# subtractor-amp03_p-stm_v1_0.net
KiCad netlist of a schematic drawn in EAGLE
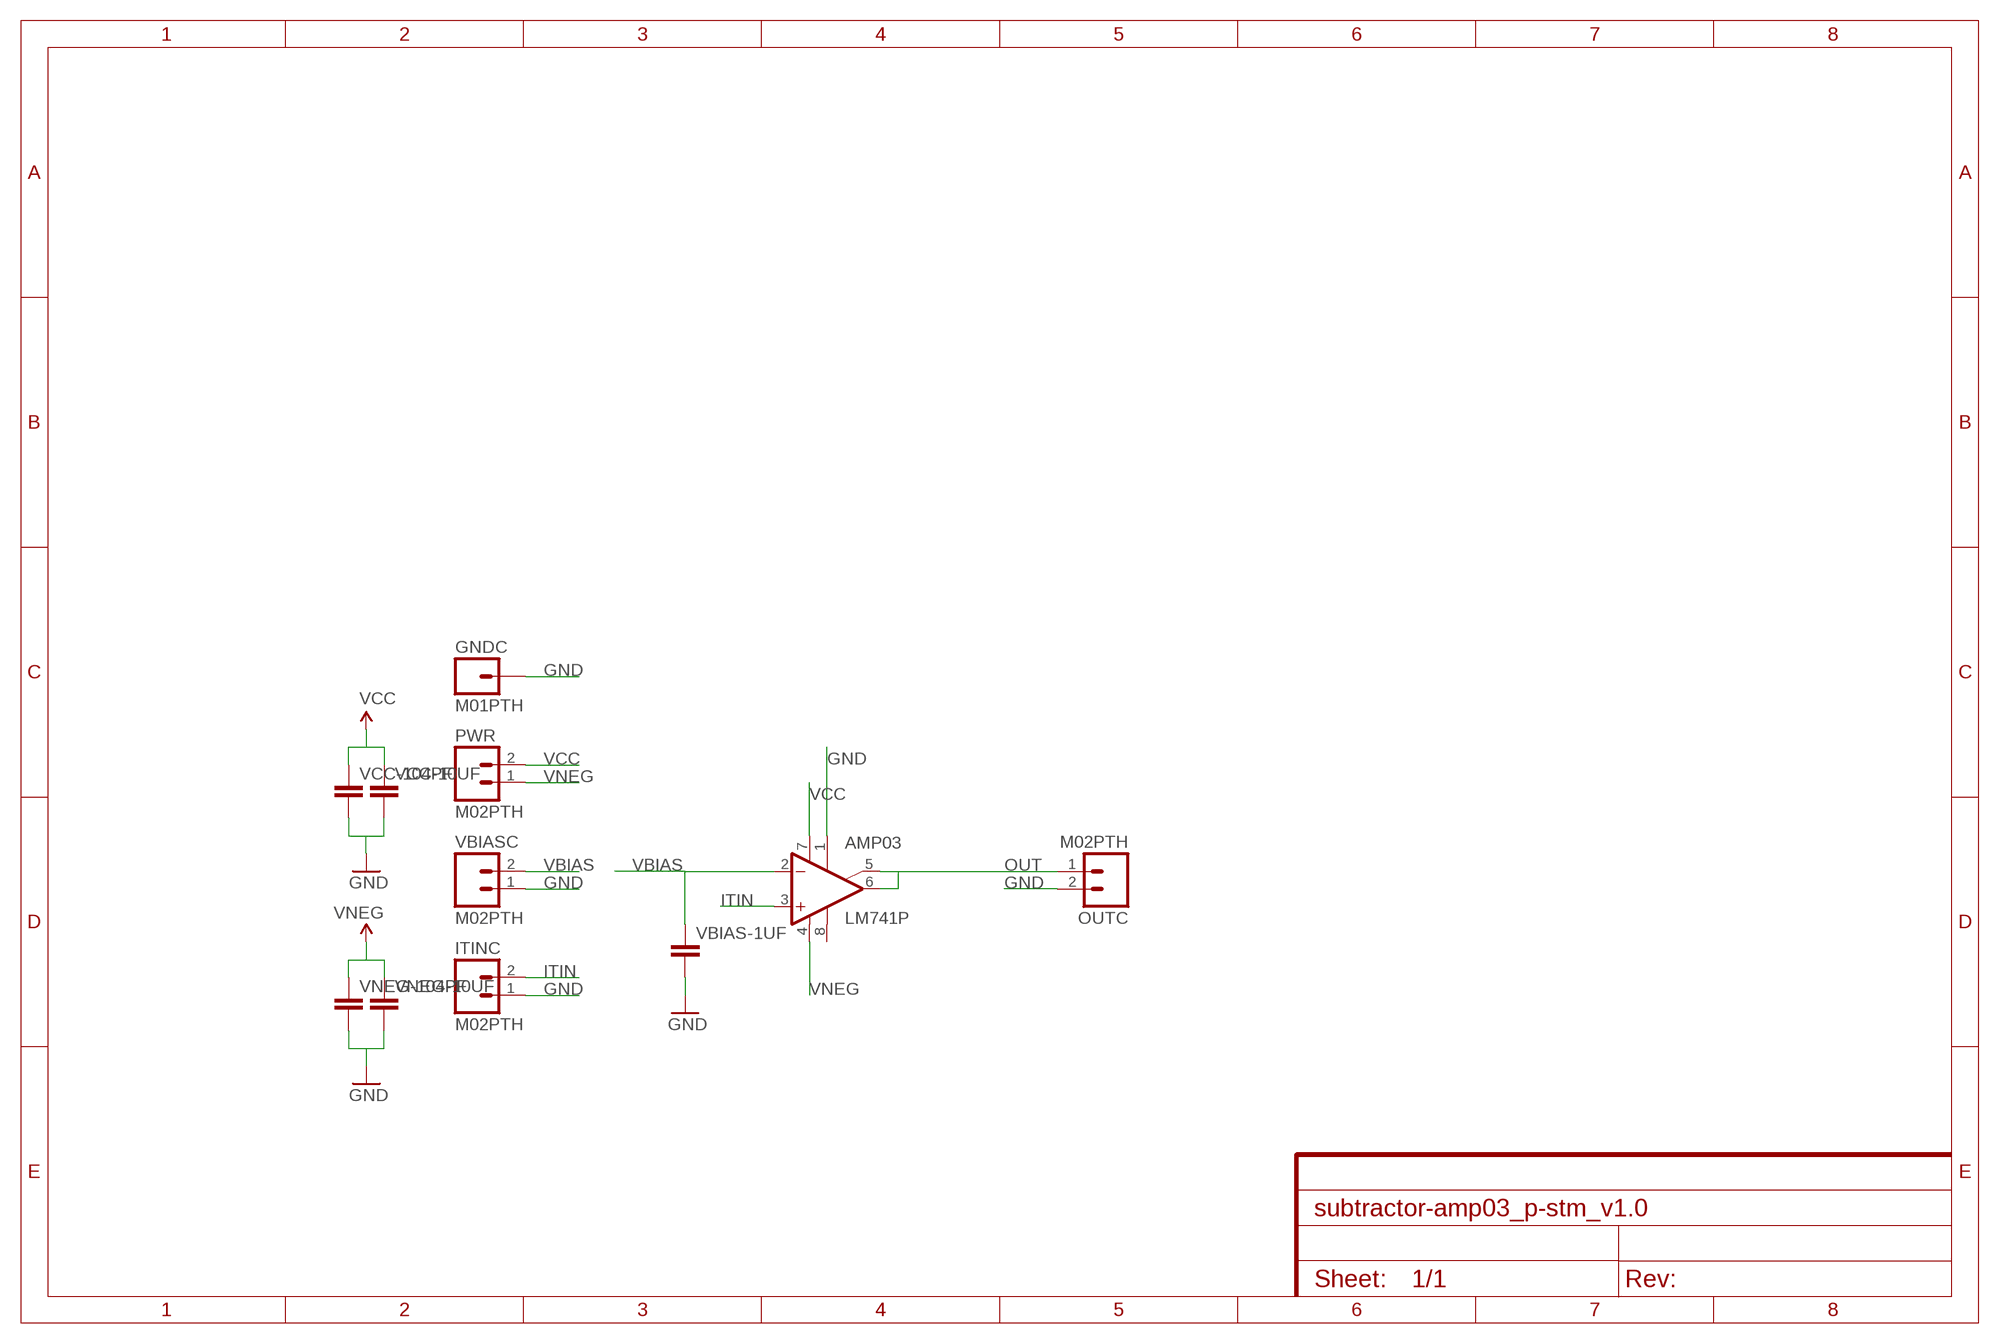
[diagram p0: schematic, sheet 1]

(export (version "E")
  (design (tool "Eeschema 10.0.6"))
  (components
    (comp (ref "AMP03")
      (value "LM741P")
      (footprint "eagle-import:DIL08")
      (libsource (lib "eagle-import") (part "741PLM"))
    )
    (comp (ref "GNDC")
      (value "M01PTH")
      (footprint "eagle-import:1X01")
      (libsource (lib "eagle-import") (part "M01PTH"))
    )
    (comp (ref "ITINC")
      (value "M02PTH")
      (footprint "eagle-import:1X02")
      (libsource (lib "eagle-import") (part "M02PTH"))
    )
    (comp (ref "OUTC")
      (value "M02PTH")
      (footprint "eagle-import:1X02")
      (libsource (lib "eagle-import") (part "M02PTH"))
    )
    (comp (ref "PWR")
      (value "M02PTH")
      (footprint "eagle-import:1X02")
      (libsource (lib "eagle-import") (part "M02PTH"))
    )
    (comp (ref "VBIAS-1UF")
      (value "CAPPTH2")
      (footprint "eagle-import:CAP-PTH-SMALL2")
      (libsource (lib "eagle-import") (part "CAPPTH2"))
    )
    (comp (ref "VBIASC")
      (value "M02PTH")
      (footprint "eagle-import:1X02")
      (libsource (lib "eagle-import") (part "M02PTH"))
    )
    (comp (ref "VCC-10UF")
      (value "CAPPTH2")
      (footprint "eagle-import:CAP-PTH-SMALL2")
      (libsource (lib "eagle-import") (part "CAPPTH2"))
    )
    (comp (ref "VCC-104PF")
      (value "CAPPTH2")
      (footprint "eagle-import:CAP-PTH-SMALL2")
      (libsource (lib "eagle-import") (part "CAPPTH2"))
    )
    (comp (ref "VNEG-10UF")
      (value "CAPPTH2")
      (footprint "eagle-import:CAP-PTH-SMALL2")
      (libsource (lib "eagle-import") (part "CAPPTH2"))
    )
    (comp (ref "VNEG-104PF")
      (value "CAPPTH2")
      (footprint "eagle-import:CAP-PTH-SMALL2")
      (libsource (lib "eagle-import") (part "CAPPTH2"))
    )
  )
  (nets
    (net (code "1") (name "/ITIN") (class "Default")
      (node (ref "AMP03") (pin "3") (pinfunction "-IN_3") (pintype "input"))
      (node (ref "ITINC") (pin "2") (pinfunction "2_2") (pintype "passive"))
    )
    (net (code "2") (name "/OUT") (class "Default")
      (node (ref "AMP03") (pin "5") (pinfunction "ON2_5") (pintype "passive"))
      (node (ref "AMP03") (pin "6") (pinfunction "OUT_6") (pintype "output"))
      (node (ref "OUTC") (pin "1") (pinfunction "1_1") (pintype "passive"))
    )
    (net (code "3") (name "/VBIAS") (class "Default")
      (node (ref "AMP03") (pin "2") (pinfunction "+IN_2") (pintype "input"))
      (node (ref "VBIAS-1UF") (pin "1") (pinfunction "1_1") (pintype "passive"))
      (node (ref "VBIASC") (pin "2") (pinfunction "2_2") (pintype "passive"))
    )
    (net (code "4") (name "GND") (class "Default")
      (node (ref "AMP03") (pin "1") (pinfunction "ON1_1") (pintype "passive"))
      (node (ref "GNDC") (pin "1") (pinfunction "1_1") (pintype "passive"))
      (node (ref "ITINC") (pin "1") (pinfunction "1_1") (pintype "passive"))
      (node (ref "OUTC") (pin "2") (pinfunction "2_2") (pintype "passive"))
      (node (ref "VBIAS-1UF") (pin "2") (pinfunction "2_2") (pintype "passive"))
      (node (ref "VBIASC") (pin "1") (pinfunction "1_1") (pintype "passive"))
      (node (ref "VCC-104PF") (pin "2") (pinfunction "2_2") (pintype "passive"))
      (node (ref "VCC-10UF") (pin "2") (pinfunction "2_2") (pintype "passive"))
      (node (ref "VNEG-104PF") (pin "2") (pinfunction "2_2") (pintype "passive"))
      (node (ref "VNEG-10UF") (pin "2") (pinfunction "2_2") (pintype "passive"))
    )
    (net (code "5") (name "VCC") (class "Default")
      (node (ref "AMP03") (pin "7") (pinfunction "V+_7") (pintype "power_in"))
      (node (ref "PWR") (pin "2") (pinfunction "2_2") (pintype "passive"))
      (node (ref "VCC-104PF") (pin "1") (pinfunction "1_1") (pintype "passive"))
      (node (ref "VCC-10UF") (pin "1") (pinfunction "1_1") (pintype "passive"))
    )
    (net (code "6") (name "VNEG") (class "Default")
      (node (ref "AMP03") (pin "4") (pinfunction "V-_4") (pintype "power_in"))
      (node (ref "PWR") (pin "1") (pinfunction "1_1") (pintype "passive"))
      (node (ref "VNEG-104PF") (pin "1") (pinfunction "1_1") (pintype "passive"))
      (node (ref "VNEG-10UF") (pin "1") (pinfunction "1_1") (pintype "passive"))
    )
    (net (code "7") (name "unconnected-(AMP03-OPT-Pad8)") (class "Default")
      (node (ref "AMP03") (pin "8") (pinfunction "OPT_8") (pintype "passive"))
    )
  )
)
